# cs301_YourGroupNumber3.net
KiCad netlist of a schematic drawn in Altium Designer
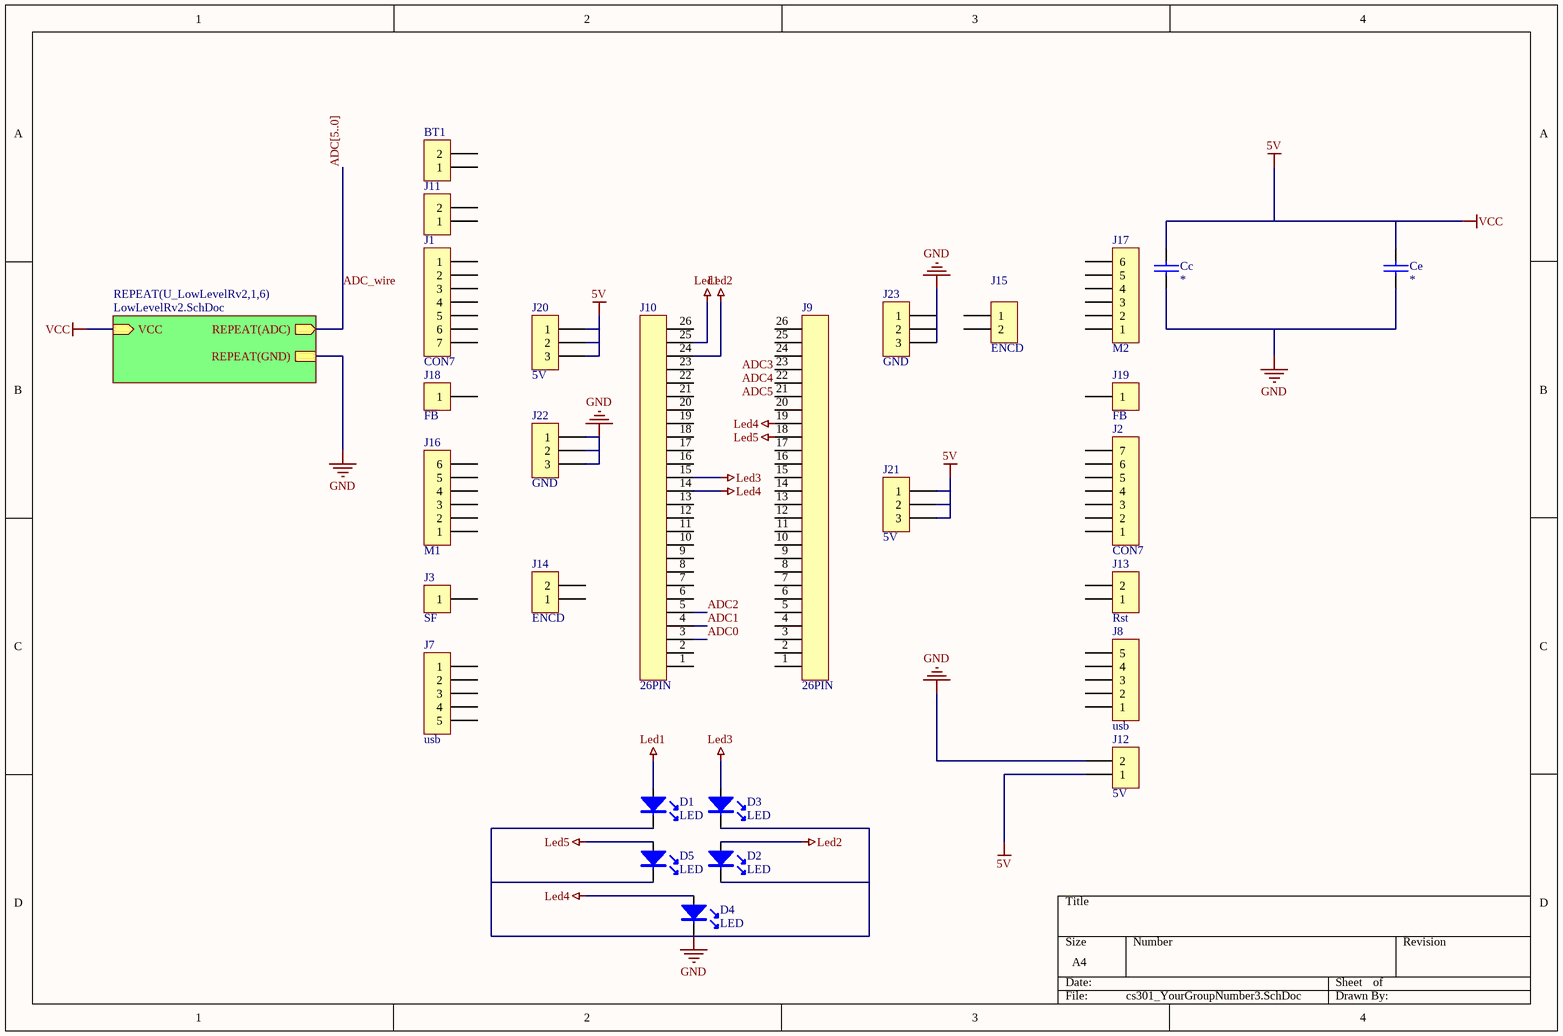
[diagram p0: cs301_YourGroupNumber3.SchDoc]

(export (version "E")
  (design (tool "Eeschema 10.0.6"))
  (components
    (comp (ref "BT1")
      (value "Battery")
      (footprint "sip2")
      (description "Connector")
      (libsource (lib "Miscellaneous Devices") (part "CON2"))
    )
    (comp (ref "Cc")
      (value "*")
      (footprint "FILM CAP-0.2")
      (description "Capacitor Non Polarised Through Hole")
      (libsource (lib "EE209V3") (part "CAP"))
    )
    (comp (ref "Ce")
      (value "*")
      (footprint "FILM CAP-0.2")
      (description "Capacitor Non Polarised Through Hole")
      (libsource (lib "EE209V3") (part "CAP"))
    )
    (comp (ref "D1") (value "LED") (footprint "LED0.1/5MM") (libsource (lib "COMSYS301_2013") (part "LED")))
    (comp (ref "D2") (value "LED") (footprint "LED0.1/5MM") (libsource (lib "COMSYS301_2013") (part "LED")))
    (comp (ref "D3") (value "LED") (footprint "LED0.1/5MM") (libsource (lib "COMSYS301_2013") (part "LED")))
    (comp (ref "D4") (value "LED") (footprint "LED0.1/5MM") (libsource (lib "COMSYS301_2013") (part "LED")))
    (comp (ref "D5") (value "LED") (footprint "LED0.1/5MM") (libsource (lib "COMSYS301_2013") (part "LED")))
    (comp (ref "J1")
      (value "CON7")
      (footprint "SIP7")
      (description "Connector")
      (libsource (lib "") (part "CON7_1"))
    )
    (comp (ref "J2")
      (value "CON7")
      (footprint "SIP7")
      (description "Connector")
      (libsource (lib "Miscellaneous Devices") (part "CON7"))
    )
    (comp (ref "J3")
      (value "SF")
      (footprint "SIP1/0.6")
      (description "Connector")
      (libsource (lib "") (part "CON1_1"))
    )
    (comp (ref "J7")
      (value "usb")
      (footprint "SIP5")
      (description "Connector")
      (libsource (lib "Miscellaneous Devices") (part "CON5"))
    )
    (comp (ref "J8")
      (value "usb")
      (footprint "SIP5")
      (description "Connector")
      (libsource (lib "") (part "CON5_1"))
    )
    (comp (ref "J9")
      (value "26PIN")
      (footprint "SIP26")
      (libsource (lib "Miscellaneous Devices") (part "26PIN"))
    )
    (comp (ref "J10") (value "26PIN") (footprint "SIP26") (libsource (lib "") (part "26PIN_1")))
    (comp (ref "J11")
      (value "Battery")
      (footprint "sip2")
      (description "Connector")
      (libsource (lib "Miscellaneous Devices") (part "CON2"))
    )
    (comp (ref "J12")
      (value "5V")
      (footprint "sip2")
      (description "Connector")
      (libsource (lib "") (part "CON2_1"))
    )
    (comp (ref "J13")
      (value "Rst")
      (footprint "sip2")
      (description "Connector")
      (libsource (lib "") (part "CON2_1"))
    )
    (comp (ref "J14")
      (value "ENCD")
      (footprint "sip2")
      (description "Connector")
      (libsource (lib "Miscellaneous Devices") (part "CON2"))
    )
    (comp (ref "J15")
      (value "ENCD")
      (footprint "sip2")
      (description "Connector")
      (libsource (lib "") (part "CON2_2"))
    )
    (comp (ref "J16")
      (value "M1")
      (footprint "sip6")
      (description "Connector")
      (libsource (lib "") (part "CON6_1"))
    )
    (comp (ref "J17")
      (value "M2")
      (footprint "sip6")
      (description "Connector")
      (libsource (lib "Miscellaneous Devices") (part "CON6"))
    )
    (comp (ref "J18")
      (value "FB")
      (footprint "SIP1/0.6")
      (description "Connector")
      (libsource (lib "Miscellaneous Devices") (part "CON1"))
    )
    (comp (ref "J19")
      (value "FB")
      (footprint "SIP1/0.6")
      (description "Connector")
      (libsource (lib "") (part "CON1_2"))
    )
    (comp (ref "J20")
      (value "5V")
      (footprint "sip3")
      (description "Connector")
      (libsource (lib "Miscellaneous Devices") (part "CON3"))
    )
    (comp (ref "J21")
      (value "5V")
      (footprint "sip3")
      (description "Connector")
      (libsource (lib "Miscellaneous Devices") (part "CON3"))
    )
    (comp (ref "J22")
      (value "GND")
      (footprint "sip3")
      (description "Connector")
      (libsource (lib "Miscellaneous Devices") (part "CON3"))
    )
    (comp (ref "J23")
      (value "GND")
      (footprint "sip3")
      (description "Connector")
      (libsource (lib "Miscellaneous Devices") (part "CON3"))
    )
  )
  (nets
    (net (code "1") (name "/ADC0") (class "Default")
      (node (ref "J10") (pin "3") (pinfunction "3_3") (pintype "passive"))
    )
    (net (code "2") (name "/ADC1") (class "Default")
      (node (ref "J10") (pin "4") (pinfunction "4_4") (pintype "passive"))
    )
    (net (code "3") (name "/ADC2") (class "Default")
      (node (ref "J10") (pin "5") (pinfunction "5_5") (pintype "passive"))
    )
    (net (code "4") (name "/ADC3") (class "Default")
      (node (ref "J9") (pin "24") (pinfunction "24_24") (pintype "passive"))
    )
    (net (code "5") (name "/ADC4") (class "Default")
      (node (ref "J9") (pin "23") (pinfunction "23_23") (pintype "passive"))
    )
    (net (code "6") (name "/ADC5") (class "Default")
      (node (ref "J9") (pin "22") (pinfunction "22_22") (pintype "passive"))
    )
    (net (code "9") (name "5V") (class "Default")
      (node (ref "Cc") (pin "1") (pinfunction "1_1") (pintype "passive"))
      (node (ref "Ce") (pin "1") (pinfunction "1_1") (pintype "passive"))
      (node (ref "J12") (pin "1") (pinfunction "1_1") (pintype "passive"))
      (node (ref "J20") (pin "1") (pinfunction "1_1") (pintype "passive"))
      (node (ref "J20") (pin "2") (pinfunction "2_2") (pintype "passive"))
      (node (ref "J20") (pin "3") (pinfunction "3_3") (pintype "passive"))
      (node (ref "J21") (pin "1") (pinfunction "1_1") (pintype "passive"))
      (node (ref "J21") (pin "2") (pinfunction "2_2") (pintype "passive"))
      (node (ref "J21") (pin "3") (pinfunction "3_3") (pintype "passive"))
    )
    (net (code "10") (name "GND") (class "Default")
      (node (ref "Cc") (pin "2") (pinfunction "2_2") (pintype "passive"))
      (node (ref "Ce") (pin "2") (pinfunction "2_2") (pintype "passive"))
      (node (ref "D1") (pin "K") (pinfunction "2_K") (pintype "passive"))
      (node (ref "D2") (pin "K") (pinfunction "2_K") (pintype "passive"))
      (node (ref "D3") (pin "K") (pinfunction "2_K") (pintype "passive"))
      (node (ref "D4") (pin "K") (pinfunction "2_K") (pintype "passive"))
      (node (ref "D5") (pin "K") (pinfunction "2_K") (pintype "passive"))
      (node (ref "J12") (pin "2") (pinfunction "2_2") (pintype "passive"))
      (node (ref "J22") (pin "1") (pinfunction "1_1") (pintype "passive"))
      (node (ref "J22") (pin "2") (pinfunction "2_2") (pintype "passive"))
      (node (ref "J22") (pin "3") (pinfunction "3_3") (pintype "passive"))
      (node (ref "J23") (pin "1") (pinfunction "1_1") (pintype "passive"))
      (node (ref "J23") (pin "2") (pinfunction "2_2") (pintype "passive"))
      (node (ref "J23") (pin "3") (pinfunction "3_3") (pintype "passive"))
    )
    (net (code "11") (name "Led1") (class "Default")
      (node (ref "D1") (pin "A") (pinfunction "1_A") (pintype "passive"))
      (node (ref "J10") (pin "25") (pinfunction "25_25") (pintype "passive"))
    )
    (net (code "12") (name "Led2") (class "Default")
      (node (ref "D2") (pin "A") (pinfunction "1_A") (pintype "passive"))
      (node (ref "J10") (pin "24") (pinfunction "24_24") (pintype "passive"))
    )
    (net (code "13") (name "Led3") (class "Default")
      (node (ref "D3") (pin "A") (pinfunction "1_A") (pintype "passive"))
      (node (ref "J10") (pin "15") (pinfunction "15_15") (pintype "passive"))
    )
    (net (code "14") (name "Led4") (class "Default")
      (node (ref "D4") (pin "A") (pinfunction "1_A") (pintype "passive"))
      (node (ref "J10") (pin "14") (pinfunction "14_14") (pintype "passive"))
      (node (ref "J9") (pin "19") (pinfunction "19_19") (pintype "passive"))
    )
    (net (code "15") (name "Led5") (class "Default")
      (node (ref "D5") (pin "A") (pinfunction "1_A") (pintype "passive"))
      (node (ref "J9") (pin "18") (pinfunction "18_18") (pintype "passive"))
    )
    (net (code "16") (name "unconnected-(BT1-Pad1)") (class "Default")
      (node (ref "BT1") (pin "1") (pinfunction "1_1") (pintype "passive"))
    )
    (net (code "17") (name "unconnected-(BT1-Pad2)") (class "Default")
      (node (ref "BT1") (pin "2") (pinfunction "2_2") (pintype "passive"))
    )
    (net (code "18") (name "unconnected-(J1-Pad1)") (class "Default")
      (node (ref "J1") (pin "1") (pinfunction "1_1") (pintype "passive"))
    )
    (net (code "19") (name "unconnected-(J1-Pad2)") (class "Default")
      (node (ref "J1") (pin "2") (pinfunction "2_2") (pintype "passive"))
    )
    (net (code "20") (name "unconnected-(J1-Pad3)") (class "Default")
      (node (ref "J1") (pin "3") (pinfunction "3_3") (pintype "passive"))
    )
    (net (code "21") (name "unconnected-(J1-Pad4)") (class "Default")
      (node (ref "J1") (pin "4") (pinfunction "4_4") (pintype "passive"))
    )
    (net (code "22") (name "unconnected-(J1-Pad5)") (class "Default")
      (node (ref "J1") (pin "5") (pinfunction "5_5") (pintype "passive"))
    )
    (net (code "23") (name "unconnected-(J1-Pad6)") (class "Default")
      (node (ref "J1") (pin "6") (pinfunction "6_6") (pintype "passive"))
    )
    (net (code "24") (name "unconnected-(J1-Pad7)") (class "Default")
      (node (ref "J1") (pin "7") (pinfunction "7_7") (pintype "passive"))
    )
    (net (code "25") (name "unconnected-(J2-Pad1)") (class "Default")
      (node (ref "J2") (pin "1") (pinfunction "1_1") (pintype "passive"))
    )
    (net (code "26") (name "unconnected-(J2-Pad2)") (class "Default")
      (node (ref "J2") (pin "2") (pinfunction "2_2") (pintype "passive"))
    )
    (net (code "27") (name "unconnected-(J2-Pad3)") (class "Default")
      (node (ref "J2") (pin "3") (pinfunction "3_3") (pintype "passive"))
    )
    (net (code "28") (name "unconnected-(J2-Pad4)") (class "Default")
      (node (ref "J2") (pin "4") (pinfunction "4_4") (pintype "passive"))
    )
    (net (code "29") (name "unconnected-(J2-Pad5)") (class "Default")
      (node (ref "J2") (pin "5") (pinfunction "5_5") (pintype "passive"))
    )
    (net (code "30") (name "unconnected-(J2-Pad6)") (class "Default")
      (node (ref "J2") (pin "6") (pinfunction "6_6") (pintype "passive"))
    )
    (net (code "31") (name "unconnected-(J2-Pad7)") (class "Default")
      (node (ref "J2") (pin "7") (pinfunction "7_7") (pintype "passive"))
    )
    (net (code "32") (name "unconnected-(J3-Pad1)") (class "Default")
      (node (ref "J3") (pin "1") (pinfunction "1_1") (pintype "passive"))
    )
    (net (code "33") (name "unconnected-(J7-Pad1)") (class "Default")
      (node (ref "J7") (pin "1") (pinfunction "1_1") (pintype "passive"))
    )
    (net (code "34") (name "unconnected-(J7-Pad2)") (class "Default")
      (node (ref "J7") (pin "2") (pinfunction "2_2") (pintype "passive"))
    )
    (net (code "35") (name "unconnected-(J7-Pad3)") (class "Default")
      (node (ref "J7") (pin "3") (pinfunction "3_3") (pintype "passive"))
    )
    (net (code "36") (name "unconnected-(J7-Pad4)") (class "Default")
      (node (ref "J7") (pin "4") (pinfunction "4_4") (pintype "passive"))
    )
    (net (code "37") (name "unconnected-(J7-Pad5)") (class "Default")
      (node (ref "J7") (pin "5") (pinfunction "5_5") (pintype "passive"))
    )
    (net (code "38") (name "unconnected-(J8-Pad1)") (class "Default")
      (node (ref "J8") (pin "1") (pinfunction "1_1") (pintype "passive"))
    )
    (net (code "39") (name "unconnected-(J8-Pad2)") (class "Default")
      (node (ref "J8") (pin "2") (pinfunction "2_2") (pintype "passive"))
    )
    (net (code "40") (name "unconnected-(J8-Pad3)") (class "Default")
      (node (ref "J8") (pin "3") (pinfunction "3_3") (pintype "passive"))
    )
    (net (code "41") (name "unconnected-(J8-Pad4)") (class "Default")
      (node (ref "J8") (pin "4") (pinfunction "4_4") (pintype "passive"))
    )
    (net (code "42") (name "unconnected-(J8-Pad5)") (class "Default")
      (node (ref "J8") (pin "5") (pinfunction "5_5") (pintype "passive"))
    )
    (net (code "43") (name "unconnected-(J9-Pad1)") (class "Default")
      (node (ref "J9") (pin "1") (pinfunction "1_1") (pintype "passive"))
    )
    (net (code "44") (name "unconnected-(J9-Pad2)") (class "Default")
      (node (ref "J9") (pin "2") (pinfunction "2_2") (pintype "passive"))
    )
    (net (code "45") (name "unconnected-(J9-Pad3)") (class "Default")
      (node (ref "J9") (pin "3") (pinfunction "3_3") (pintype "passive"))
    )
    (net (code "46") (name "unconnected-(J9-Pad4)") (class "Default")
      (node (ref "J9") (pin "4") (pinfunction "4_4") (pintype "passive"))
    )
    (net (code "47") (name "unconnected-(J9-Pad5)") (class "Default")
      (node (ref "J9") (pin "5") (pinfunction "5_5") (pintype "passive"))
    )
    (net (code "48") (name "unconnected-(J9-Pad6)") (class "Default")
      (node (ref "J9") (pin "6") (pinfunction "6_6") (pintype "passive"))
    )
    (net (code "49") (name "unconnected-(J9-Pad7)") (class "Default")
      (node (ref "J9") (pin "7") (pinfunction "7_7") (pintype "passive"))
    )
    (net (code "50") (name "unconnected-(J9-Pad8)") (class "Default")
      (node (ref "J9") (pin "8") (pinfunction "8_8") (pintype "passive"))
    )
    (net (code "51") (name "unconnected-(J9-Pad9)") (class "Default")
      (node (ref "J9") (pin "9") (pinfunction "9_9") (pintype "passive"))
    )
    (net (code "52") (name "unconnected-(J9-Pad10)") (class "Default")
      (node (ref "J9") (pin "10") (pinfunction "10_10") (pintype "passive"))
    )
    (net (code "53") (name "unconnected-(J9-Pad11)") (class "Default")
      (node (ref "J9") (pin "11") (pinfunction "11_11") (pintype "passive"))
    )
    (net (code "54") (name "unconnected-(J9-Pad12)") (class "Default")
      (node (ref "J9") (pin "12") (pinfunction "12_12") (pintype "passive"))
    )
    (net (code "55") (name "unconnected-(J9-Pad13)") (class "Default")
      (node (ref "J9") (pin "13") (pinfunction "13_13") (pintype "passive"))
    )
    (net (code "56") (name "unconnected-(J9-Pad14)") (class "Default")
      (node (ref "J9") (pin "14") (pinfunction "14_14") (pintype "passive"))
    )
    (net (code "57") (name "unconnected-(J9-Pad15)") (class "Default")
      (node (ref "J9") (pin "15") (pinfunction "15_15") (pintype "passive"))
    )
    (net (code "58") (name "unconnected-(J9-Pad16)") (class "Default")
      (node (ref "J9") (pin "16") (pinfunction "16_16") (pintype "passive"))
    )
    (net (code "59") (name "unconnected-(J9-Pad17)") (class "Default")
      (node (ref "J9") (pin "17") (pinfunction "17_17") (pintype "passive"))
    )
    (net (code "60") (name "unconnected-(J9-Pad20)") (class "Default")
      (node (ref "J9") (pin "20") (pinfunction "20_20") (pintype "passive"))
    )
    (net (code "61") (name "unconnected-(J9-Pad21)") (class "Default")
      (node (ref "J9") (pin "21") (pinfunction "21_21") (pintype "passive"))
    )
    (net (code "62") (name "unconnected-(J9-Pad25)") (class "Default")
      (node (ref "J9") (pin "25") (pinfunction "25_25") (pintype "passive"))
    )
    (net (code "63") (name "unconnected-(J9-Pad26)") (class "Default")
      (node (ref "J9") (pin "26") (pinfunction "26_26") (pintype "passive"))
    )
    (net (code "64") (name "unconnected-(J10-Pad1)") (class "Default")
      (node (ref "J10") (pin "1") (pinfunction "1_1") (pintype "passive"))
    )
    (net (code "65") (name "unconnected-(J10-Pad2)") (class "Default")
      (node (ref "J10") (pin "2") (pinfunction "2_2") (pintype "passive"))
    )
    (net (code "66") (name "unconnected-(J10-Pad6)") (class "Default")
      (node (ref "J10") (pin "6") (pinfunction "6_6") (pintype "passive"))
    )
    (net (code "67") (name "unconnected-(J10-Pad7)") (class "Default")
      (node (ref "J10") (pin "7") (pinfunction "7_7") (pintype "passive"))
    )
    (net (code "68") (name "unconnected-(J10-Pad8)") (class "Default")
      (node (ref "J10") (pin "8") (pinfunction "8_8") (pintype "passive"))
    )
    (net (code "69") (name "unconnected-(J10-Pad9)") (class "Default")
      (node (ref "J10") (pin "9") (pinfunction "9_9") (pintype "passive"))
    )
    (net (code "70") (name "unconnected-(J10-Pad10)") (class "Default")
      (node (ref "J10") (pin "10") (pinfunction "10_10") (pintype "passive"))
    )
    (net (code "71") (name "unconnected-(J10-Pad11)") (class "Default")
      (node (ref "J10") (pin "11") (pinfunction "11_11") (pintype "passive"))
    )
    (net (code "72") (name "unconnected-(J10-Pad12)") (class "Default")
      (node (ref "J10") (pin "12") (pinfunction "12_12") (pintype "passive"))
    )
    (net (code "73") (name "unconnected-(J10-Pad13)") (class "Default")
      (node (ref "J10") (pin "13") (pinfunction "13_13") (pintype "passive"))
    )
    (net (code "74") (name "unconnected-(J10-Pad16)") (class "Default")
      (node (ref "J10") (pin "16") (pinfunction "16_16") (pintype "passive"))
    )
    (net (code "75") (name "unconnected-(J10-Pad17)") (class "Default")
      (node (ref "J10") (pin "17") (pinfunction "17_17") (pintype "passive"))
    )
    (net (code "76") (name "unconnected-(J10-Pad18)") (class "Default")
      (node (ref "J10") (pin "18") (pinfunction "18_18") (pintype "passive"))
    )
    (net (code "77") (name "unconnected-(J10-Pad19)") (class "Default")
      (node (ref "J10") (pin "19") (pinfunction "19_19") (pintype "passive"))
    )
    (net (code "78") (name "unconnected-(J10-Pad20)") (class "Default")
      (node (ref "J10") (pin "20") (pinfunction "20_20") (pintype "passive"))
    )
    (net (code "79") (name "unconnected-(J10-Pad21)") (class "Default")
      (node (ref "J10") (pin "21") (pinfunction "21_21") (pintype "passive"))
    )
    (net (code "80") (name "unconnected-(J10-Pad22)") (class "Default")
      (node (ref "J10") (pin "22") (pinfunction "22_22") (pintype "passive"))
    )
    (net (code "81") (name "unconnected-(J10-Pad23)") (class "Default")
      (node (ref "J10") (pin "23") (pinfunction "23_23") (pintype "passive"))
    )
    (net (code "82") (name "unconnected-(J10-Pad26)") (class "Default")
      (node (ref "J10") (pin "26") (pinfunction "26_26") (pintype "passive"))
    )
    (net (code "83") (name "unconnected-(J11-Pad1)") (class "Default")
      (node (ref "J11") (pin "1") (pinfunction "1_1") (pintype "passive"))
    )
    (net (code "84") (name "unconnected-(J11-Pad2)") (class "Default")
      (node (ref "J11") (pin "2") (pinfunction "2_2") (pintype "passive"))
    )
    (net (code "85") (name "unconnected-(J13-Pad1)") (class "Default")
      (node (ref "J13") (pin "1") (pinfunction "1_1") (pintype "passive"))
    )
    (net (code "86") (name "unconnected-(J13-Pad2)") (class "Default")
      (node (ref "J13") (pin "2") (pinfunction "2_2") (pintype "passive"))
    )
    (net (code "87") (name "unconnected-(J14-Pad1)") (class "Default")
      (node (ref "J14") (pin "1") (pinfunction "1_1") (pintype "passive"))
    )
    (net (code "88") (name "unconnected-(J14-Pad2)") (class "Default")
      (node (ref "J14") (pin "2") (pinfunction "2_2") (pintype "passive"))
    )
    (net (code "89") (name "unconnected-(J15-Pad1)") (class "Default")
      (node (ref "J15") (pin "1") (pinfunction "1_1") (pintype "passive"))
    )
    (net (code "90") (name "unconnected-(J15-Pad2)") (class "Default")
      (node (ref "J15") (pin "2") (pinfunction "2_2") (pintype "passive"))
    )
    (net (code "91") (name "unconnected-(J16-Pad1)") (class "Default")
      (node (ref "J16") (pin "1") (pinfunction "1_1") (pintype "passive"))
    )
    (net (code "92") (name "unconnected-(J16-Pad2)") (class "Default")
      (node (ref "J16") (pin "2") (pinfunction "2_2") (pintype "passive"))
    )
    (net (code "93") (name "unconnected-(J16-Pad3)") (class "Default")
      (node (ref "J16") (pin "3") (pinfunction "3_3") (pintype "passive"))
    )
    (net (code "94") (name "unconnected-(J16-Pad4)") (class "Default")
      (node (ref "J16") (pin "4") (pinfunction "4_4") (pintype "passive"))
    )
    (net (code "95") (name "unconnected-(J16-Pad5)") (class "Default")
      (node (ref "J16") (pin "5") (pinfunction "5_5") (pintype "passive"))
    )
    (net (code "96") (name "unconnected-(J16-Pad6)") (class "Default")
      (node (ref "J16") (pin "6") (pinfunction "6_6") (pintype "passive"))
    )
    (net (code "97") (name "unconnected-(J17-Pad1)") (class "Default")
      (node (ref "J17") (pin "1") (pinfunction "1_1") (pintype "passive"))
    )
    (net (code "98") (name "unconnected-(J17-Pad2)") (class "Default")
      (node (ref "J17") (pin "2") (pinfunction "2_2") (pintype "passive"))
    )
    (net (code "99") (name "unconnected-(J17-Pad3)") (class "Default")
      (node (ref "J17") (pin "3") (pinfunction "3_3") (pintype "passive"))
    )
    (net (code "100") (name "unconnected-(J17-Pad4)") (class "Default")
      (node (ref "J17") (pin "4") (pinfunction "4_4") (pintype "passive"))
    )
    (net (code "101") (name "unconnected-(J17-Pad5)") (class "Default")
      (node (ref "J17") (pin "5") (pinfunction "5_5") (pintype "passive"))
    )
    (net (code "102") (name "unconnected-(J17-Pad6)") (class "Default")
      (node (ref "J17") (pin "6") (pinfunction "6_6") (pintype "passive"))
    )
    (net (code "103") (name "unconnected-(J18-Pad1)") (class "Default")
      (node (ref "J18") (pin "1") (pinfunction "1_1") (pintype "passive"))
    )
    (net (code "104") (name "unconnected-(J19-Pad1)") (class "Default")
      (node (ref "J19") (pin "1") (pinfunction "1_1") (pintype "passive"))
    )
  )
)
